# ir_single.net
KiCad netlist of a schematic drawn in EAGLE
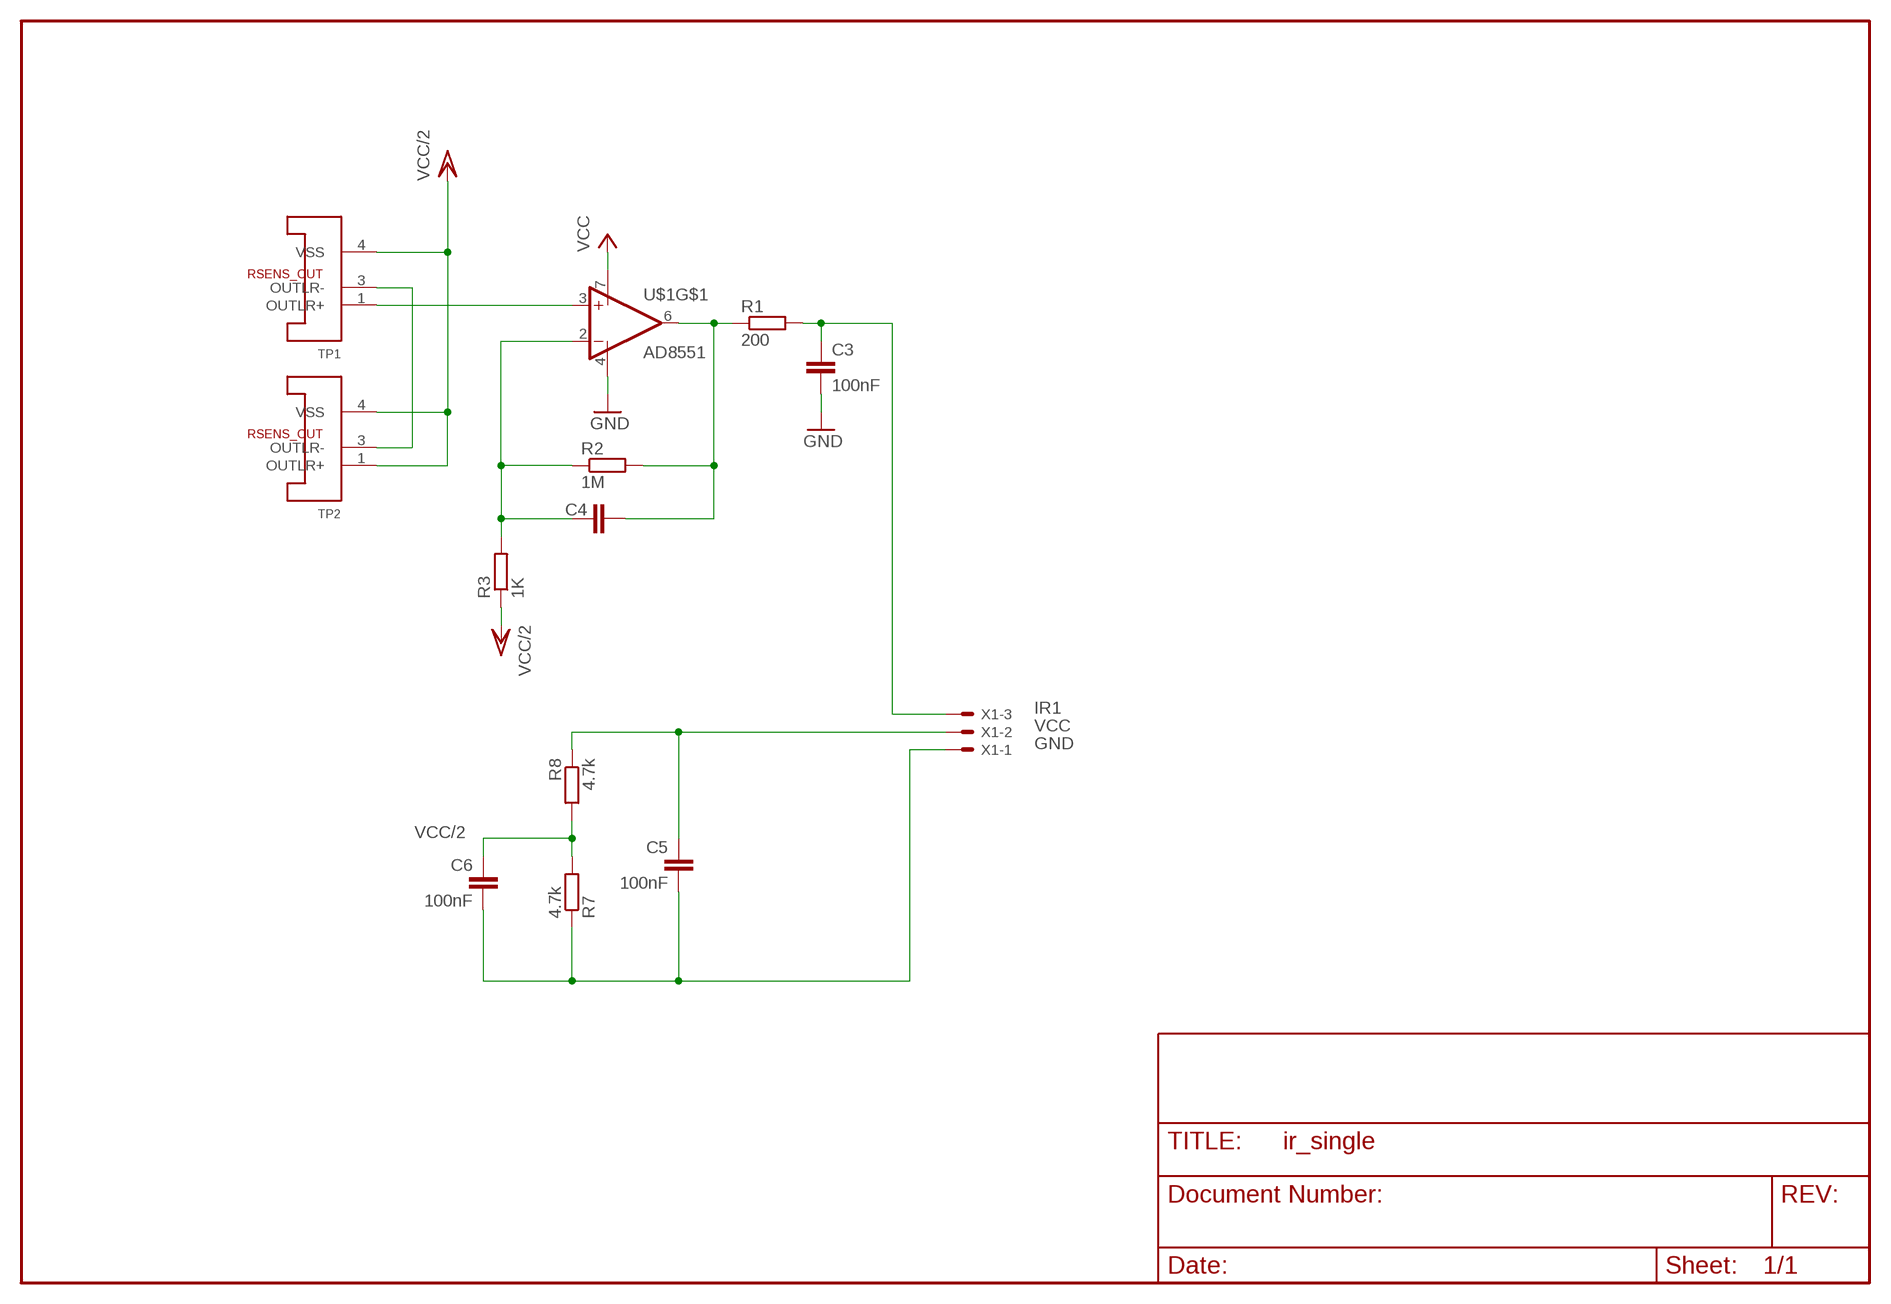
[diagram p0: schematic, sheet 1]

(export (version "E")
  (design (tool "Eeschema 10.0.6"))
  (components
    (comp (ref "C3")
      (value "100nF")
      (footprint "eagle-import:C0603")
      (libsource (lib "eagle-import") (part "C-EUC0603"))
    )
    (comp (ref "C4")
      (value "C-EUC0603")
      (footprint "eagle-import:C0603")
      (libsource (lib "eagle-import") (part "C-EUC0603"))
    )
    (comp (ref "C5")
      (value "100nF")
      (footprint "eagle-import:C0603")
      (libsource (lib "eagle-import") (part "C-EUC0603"))
    )
    (comp (ref "C6")
      (value "100nF")
      (footprint "eagle-import:C0603")
      (libsource (lib "eagle-import") (part "C-EUC0603"))
    )
    (comp (ref "R1")
      (value "200")
      (footprint "eagle-import:R0603")
      (libsource (lib "eagle-import") (part "R-EU_R0603"))
    )
    (comp (ref "R2")
      (value "1M")
      (footprint "eagle-import:R0603")
      (libsource (lib "eagle-import") (part "R-EU_R0603"))
    )
    (comp (ref "R3")
      (value "1K")
      (footprint "eagle-import:R0603")
      (libsource (lib "eagle-import") (part "R-EU_R0603"))
    )
    (comp (ref "R7")
      (value "4.7k")
      (footprint "eagle-import:R0603")
      (libsource (lib "eagle-import") (part "R-EU_R0603"))
    )
    (comp (ref "R8")
      (value "4.7k")
      (footprint "eagle-import:R0603")
      (libsource (lib "eagle-import") (part "R-EU_R0603"))
    )
    (comp (ref "TP1")
      (value "MLX90247")
      (footprint "eagle-import:TO39H")
      (libsource (lib "eagle-import") (part "MLX90247"))
    )
    (comp (ref "TP2")
      (value "MLX90247")
      (footprint "eagle-import:TO39H")
      (libsource (lib "eagle-import") (part "MLX90247"))
    )
    (comp (ref "U$1")
      (value "AD8551")
      (footprint "eagle-import:MSOP8")
      (libsource (lib "eagle-import") (part "AD8551"))
    )
    (comp (ref "X1")
      (value "53047-03")
      (footprint "eagle-import:53047-03")
      (libsource (lib "eagle-import") (part "53?-03047"))
    )
  )
  (nets
    (net (code "1") (name "/IR1") (class "Default")
      (node (ref "C3") (pin "1") (pinfunction "1_1") (pintype "passive"))
      (node (ref "R1") (pin "2") (pinfunction "2_2") (pintype "passive"))
      (node (ref "X1") (pin "3") (pinfunction "S_3") (pintype "passive"))
    )
    (net (code "2") (name "GND") (class "Default")
      (node (ref "C3") (pin "2") (pinfunction "2_2") (pintype "passive"))
      (node (ref "C5") (pin "2") (pinfunction "2_2") (pintype "passive"))
      (node (ref "C6") (pin "2") (pinfunction "2_2") (pintype "passive"))
      (node (ref "R7") (pin "1") (pinfunction "1_1") (pintype "passive"))
      (node (ref "U$1") (pin "4") (pinfunction "V-_4") (pintype "power_in"))
      (node (ref "X1") (pin "1") (pinfunction "S_1") (pintype "passive"))
    )
    (net (code "3") (name "Net-(TP1-OUTLR+)") (class "Default")
      (node (ref "TP1") (pin "1") (pinfunction "OUTLR+_1") (pintype "bidirectional"))
      (node (ref "U$1") (pin "3") (pinfunction "+IN_3") (pintype "input"))
    )
    (net (code "4") (name "Net-(TP1-OUTLR-)") (class "Default")
      (node (ref "TP1") (pin "3") (pinfunction "OUTLR-_3") (pintype "bidirectional"))
      (node (ref "TP2") (pin "3") (pinfunction "OUTLR-_3") (pintype "bidirectional"))
    )
    (net (code "5") (name "Net-(U$1A--IN)") (class "Default")
      (node (ref "C4") (pin "1") (pinfunction "1_1") (pintype "passive"))
      (node (ref "R2") (pin "1") (pinfunction "1_1") (pintype "passive"))
      (node (ref "R3") (pin "2") (pinfunction "2_2") (pintype "passive"))
      (node (ref "U$1") (pin "2") (pinfunction "-IN_2") (pintype "input"))
    )
    (net (code "6") (name "Net-(U$1A-OUT)") (class "Default")
      (node (ref "C4") (pin "2") (pinfunction "2_2") (pintype "passive"))
      (node (ref "R1") (pin "1") (pinfunction "1_1") (pintype "passive"))
      (node (ref "R2") (pin "2") (pinfunction "2_2") (pintype "passive"))
      (node (ref "U$1") (pin "6") (pinfunction "OUT_6") (pintype "output"))
    )
    (net (code "7") (name "VCC") (class "Default")
      (node (ref "C5") (pin "1") (pinfunction "1_1") (pintype "passive"))
      (node (ref "R8") (pin "1") (pinfunction "1_1") (pintype "passive"))
      (node (ref "U$1") (pin "7") (pinfunction "V+_7") (pintype "power_in"))
      (node (ref "X1") (pin "2") (pinfunction "S_2") (pintype "passive"))
    )
    (net (code "8") (name "VCC{slash}2") (class "Default")
      (node (ref "C6") (pin "1") (pinfunction "1_1") (pintype "passive"))
      (node (ref "R3") (pin "1") (pinfunction "1_1") (pintype "passive"))
      (node (ref "R7") (pin "2") (pinfunction "2_2") (pintype "passive"))
      (node (ref "R8") (pin "2") (pinfunction "2_2") (pintype "passive"))
      (node (ref "TP1") (pin "4") (pinfunction "VSS_4") (pintype "bidirectional"))
      (node (ref "TP2") (pin "1") (pinfunction "OUTLR+_1") (pintype "bidirectional"))
      (node (ref "TP2") (pin "4") (pinfunction "VSS_4") (pintype "bidirectional"))
    )
  )
)
